# sm_watch.net
KiCad netlist of a schematic drawn in EAGLE
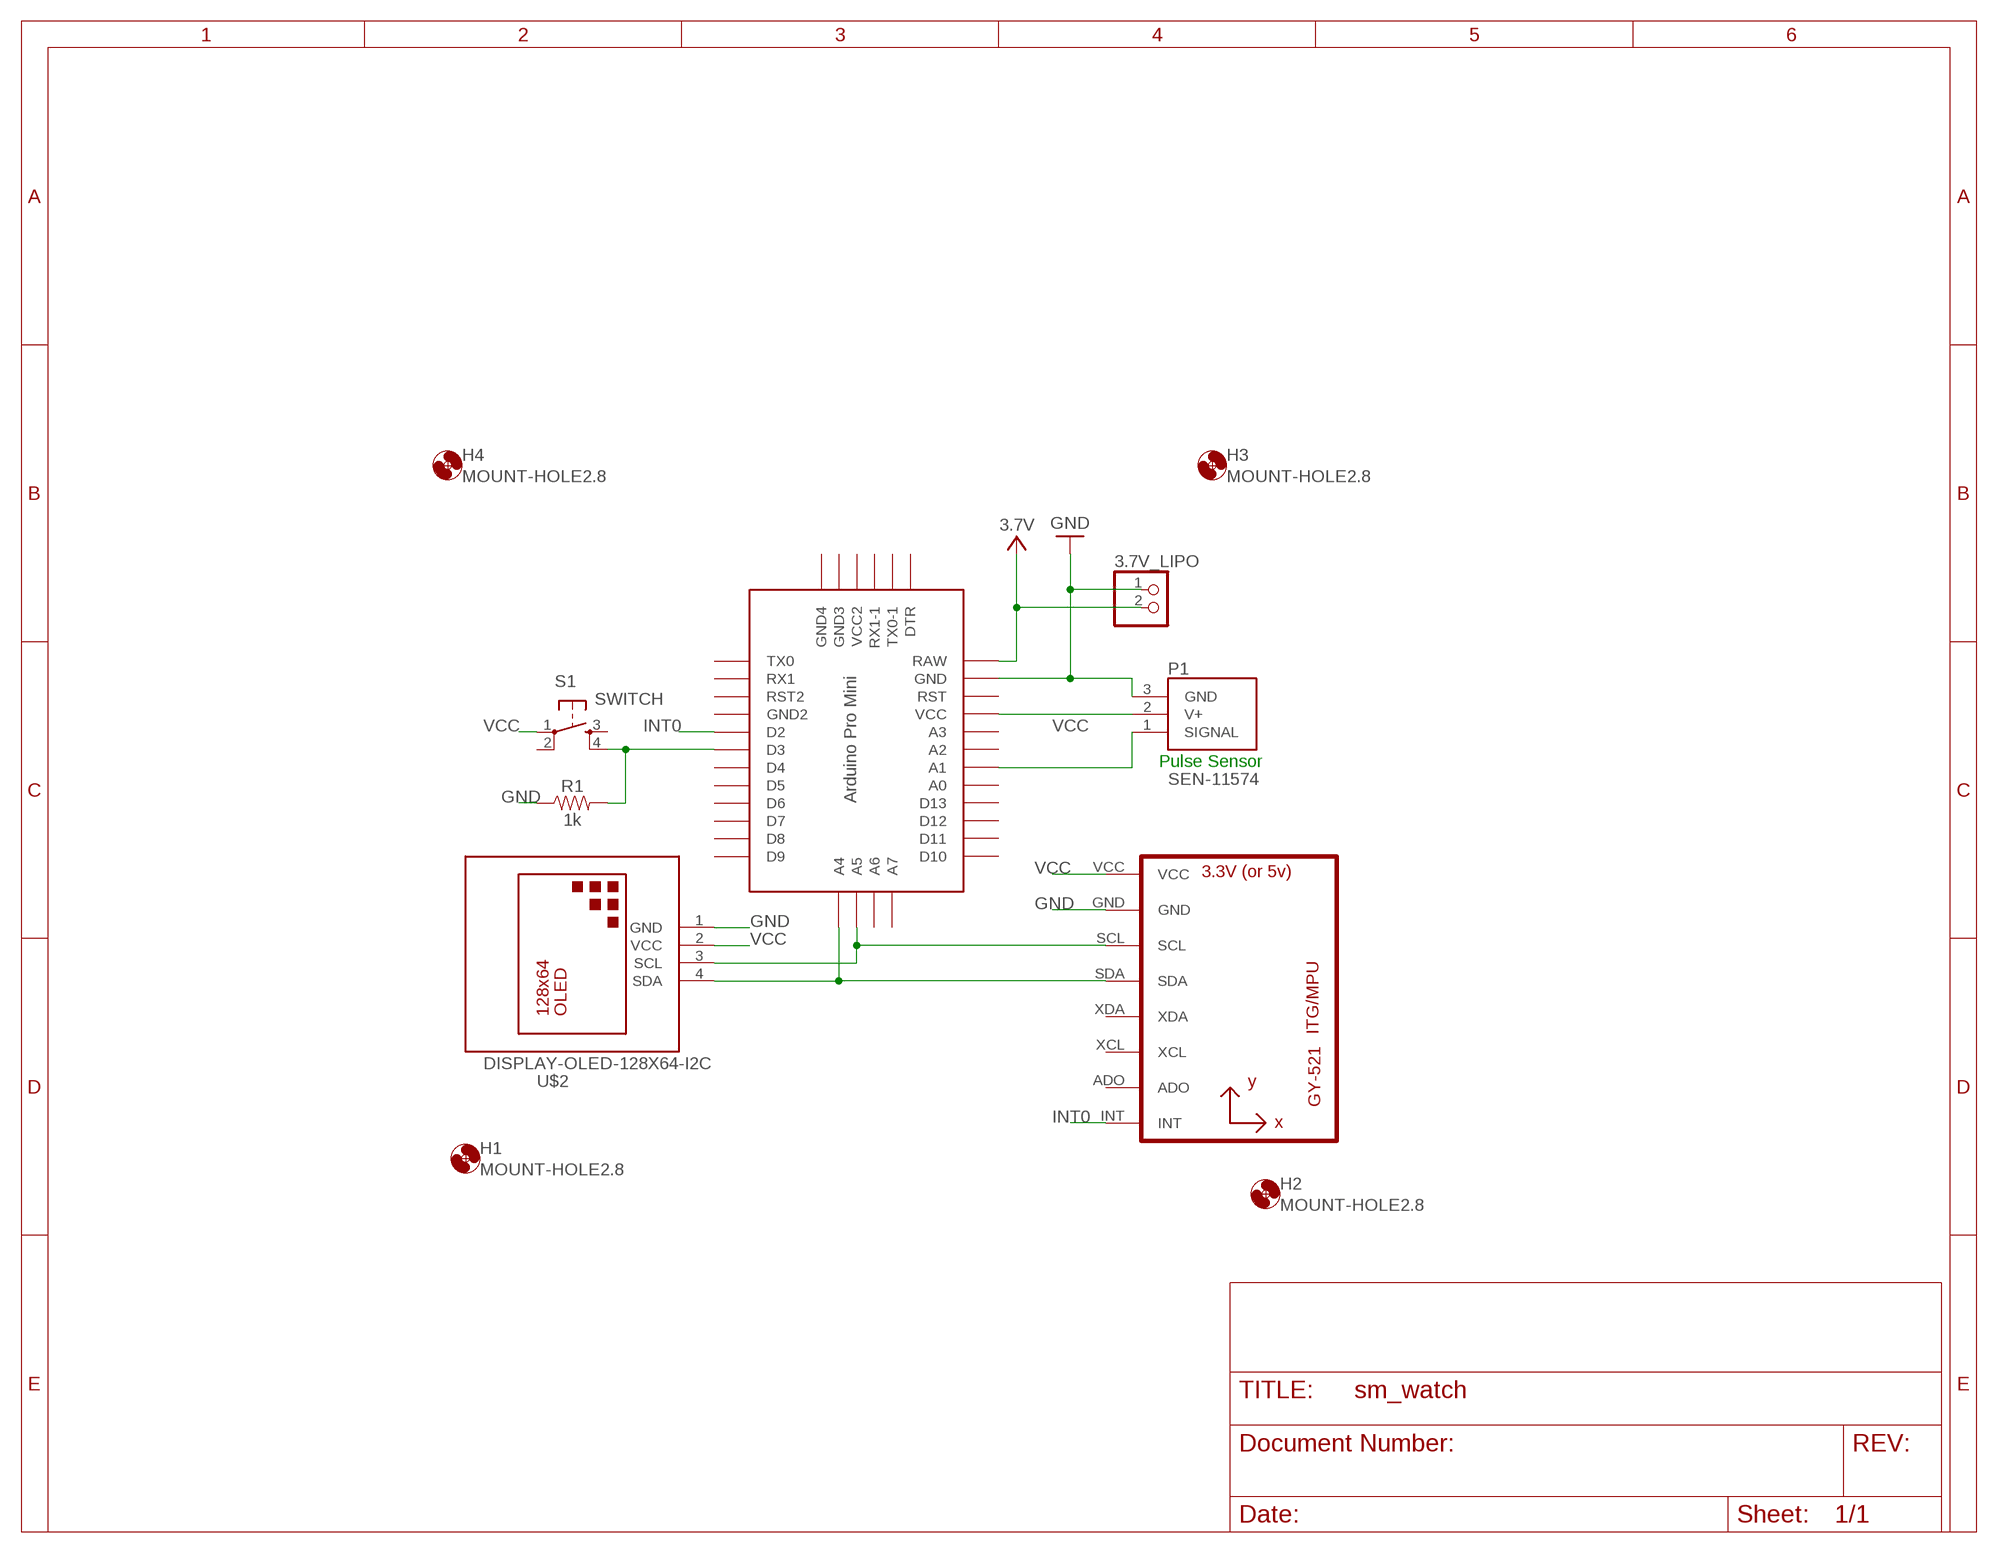
[diagram p0: schematic, sheet 1]

(export (version "E")
  (design (tool "Eeschema 10.0.6"))
  (components
    (comp (ref "3.7V_LIPO")
      (value "PINHD-1X2/90")
      (footprint "eagle-import:1X02_90")
      (libsource (lib "eagle-import") (part "PINHD-1X2/90"))
    )
    (comp (ref "H1")
      (value "MOUNT-HOLE2.8")
      (footprint "eagle-import:2,8")
      (libsource (lib "eagle-import") (part "MOUNT-HOLE2.8"))
    )
    (comp (ref "H2")
      (value "MOUNT-HOLE2.8")
      (footprint "eagle-import:2,8")
      (libsource (lib "eagle-import") (part "MOUNT-HOLE2.8"))
    )
    (comp (ref "H3")
      (value "MOUNT-HOLE2.8")
      (footprint "eagle-import:2,8")
      (libsource (lib "eagle-import") (part "MOUNT-HOLE2.8"))
    )
    (comp (ref "H4")
      (value "MOUNT-HOLE2.8")
      (footprint "eagle-import:2,8")
      (libsource (lib "eagle-import") (part "MOUNT-HOLE2.8"))
    )
    (comp (ref "P1")
      (value "SEN-11574")
      (footprint "eagle-import:XDCR_SEN-11574")
      (fields (field (name "MF") "SparkFun"))
      (libsource (lib "eagle-import") (part "SEN-11574"))
    )
    (comp (ref "R1")
      (value "1k")
      (footprint "eagle-import:0402-TIGHT")
      (libsource (lib "eagle-import") (part "1KOHM-0402T-1/16W-1%"))
    )
    (comp (ref "S1")
      (value "SWITCH")
      (footprint "eagle-import:DTS-6")
      (libsource (lib "eagle-import") (part "DTS-6"))
    )
    (comp (ref "U$1")
      (value "PRO-MINI")
      (footprint "eagle-import:PRO-MINI")
      (libsource (lib "eagle-import") (part "PRO-MINI"))
    )
    (comp (ref "U$2")
      (value "DISPLAY-OLED-128X64-I2C")
      (footprint "eagle-import:DISPLAY-OLED-128X64-I2C")
      (libsource (lib "eagle-import") (part "DISPLAY-OLED-128X64-I2C"))
    )
    (comp (ref "U1")
      (value "GY-521MPU6050")
      (footprint "eagle-import:GY-521")
      (libsource (lib "eagle-import") (part "GY-521MPU6050"))
    )
  )
  (nets
    (net (code "1") (name "/INT0") (class "Default")
      (node (ref "U$1") (pin "D2") (pinfunction "D2_D2") (pintype "bidirectional"))
      (node (ref "U1") (pin "INT") (pinfunction "INT_INT") (pintype "bidirectional"))
    )
    (net (code "2") (name "/VCC") (class "Default")
      (node (ref "P1") (pin "2") (pinfunction "V+_2") (pintype "power_in"))
      (node (ref "S1") (pin "1") (pinfunction "1_1") (pintype "passive"))
      (node (ref "U$1") (pin "VCC") (pinfunction "VCC_VCC") (pintype "bidirectional"))
      (node (ref "U$2") (pin "2") (pinfunction "VCC_2") (pintype "power_in"))
      (node (ref "U1") (pin "VCC") (pinfunction "VCC_VCC") (pintype "bidirectional"))
    )
    (net (code "3") (name "3.7V") (class "Default")
      (node (ref "3.7V_LIPO") (pin "2") (pinfunction "2_2") (pintype "passive"))
      (node (ref "U$1") (pin "RAW") (pinfunction "RAW_RAW") (pintype "power_in"))
    )
    (net (code "4") (name "GND") (class "Default")
      (node (ref "3.7V_LIPO") (pin "1") (pinfunction "1_1") (pintype "passive"))
      (node (ref "P1") (pin "3") (pinfunction "GND_3") (pintype "power_in"))
      (node (ref "R1") (pin "1") (pinfunction "1_1") (pintype "passive"))
      (node (ref "U$1") (pin "GND") (pinfunction "GND_GND") (pintype "input"))
      (node (ref "U$2") (pin "1") (pinfunction "GND_1") (pintype "power_in"))
      (node (ref "U1") (pin "GND") (pinfunction "GND_GND") (pintype "bidirectional"))
    )
    (net (code "5") (name "Net-(P1-SIGNAL)") (class "Default")
      (node (ref "P1") (pin "1") (pinfunction "SIGNAL_1") (pintype "bidirectional"))
      (node (ref "U$1") (pin "A1") (pinfunction "A1_A1") (pintype "bidirectional"))
    )
    (net (code "6") (name "Net-(R1-Pad2)") (class "Default")
      (node (ref "R1") (pin "2") (pinfunction "2_2") (pintype "passive"))
      (node (ref "S1") (pin "4") (pinfunction "4_4") (pintype "passive"))
      (node (ref "U$1") (pin "D3") (pinfunction "D3_D3") (pintype "bidirectional"))
    )
    (net (code "7") (name "Net-(U$2-SCL)") (class "Default")
      (node (ref "U$1") (pin "A5") (pinfunction "A5_A5") (pintype "bidirectional"))
      (node (ref "U$2") (pin "3") (pinfunction "SCL_3") (pintype "bidirectional"))
      (node (ref "U1") (pin "SCL") (pinfunction "SCL_SCL") (pintype "bidirectional"))
    )
    (net (code "8") (name "Net-(U$2-SDA)") (class "Default")
      (node (ref "U$1") (pin "A4") (pinfunction "A4_A4") (pintype "bidirectional"))
      (node (ref "U$2") (pin "4") (pinfunction "SDA_4") (pintype "bidirectional"))
      (node (ref "U1") (pin "SDA") (pinfunction "SDA_SDA") (pintype "bidirectional"))
    )
    (net (code "9") (name "unconnected-(S1-Pad2)") (class "Default")
      (node (ref "S1") (pin "2") (pinfunction "2_2") (pintype "passive"))
    )
    (net (code "10") (name "unconnected-(S1-Pad3)") (class "Default")
      (node (ref "S1") (pin "3") (pinfunction "3_3") (pintype "passive"))
    )
    (net (code "11") (name "unconnected-(U$1-GND2-PadGND1)") (class "Default")
      (node (ref "U$1") (pin "GND1") (pinfunction "GND2_GND1") (pintype "bidirectional"))
    )
    (net (code "12") (name "unconnected-(U$1-GND4-PadGND2)") (class "Default")
      (node (ref "U$1") (pin "GND2") (pinfunction "GND4_GND2") (pintype "bidirectional"))
    )
    (net (code "13") (name "unconnected-(U$1-PadA0)") (class "Default")
      (node (ref "U$1") (pin "A0") (pinfunction "A0_A0") (pintype "bidirectional"))
    )
    (net (code "14") (name "unconnected-(U$1-PadA2)") (class "Default")
      (node (ref "U$1") (pin "A2") (pinfunction "A2_A2") (pintype "bidirectional"))
    )
    (net (code "15") (name "unconnected-(U$1-PadA3)") (class "Default")
      (node (ref "U$1") (pin "A3") (pinfunction "A3_A3") (pintype "bidirectional"))
    )
    (net (code "16") (name "unconnected-(U$1-PadA6)") (class "Default")
      (node (ref "U$1") (pin "A6") (pinfunction "A6_A6") (pintype "bidirectional"))
    )
    (net (code "17") (name "unconnected-(U$1-PadA7)") (class "Default")
      (node (ref "U$1") (pin "A7") (pinfunction "A7_A7") (pintype "bidirectional"))
    )
    (net (code "18") (name "unconnected-(U$1-PadD4)") (class "Default")
      (node (ref "U$1") (pin "D4") (pinfunction "D4_D4") (pintype "bidirectional"))
    )
    (net (code "19") (name "unconnected-(U$1-PadD5)") (class "Default")
      (node (ref "U$1") (pin "D5") (pinfunction "D5_D5") (pintype "bidirectional"))
    )
    (net (code "20") (name "unconnected-(U$1-PadD6)") (class "Default")
      (node (ref "U$1") (pin "D6") (pinfunction "D6_D6") (pintype "bidirectional"))
    )
    (net (code "21") (name "unconnected-(U$1-PadD7)") (class "Default")
      (node (ref "U$1") (pin "D7") (pinfunction "D7_D7") (pintype "bidirectional"))
    )
    (net (code "22") (name "unconnected-(U$1-PadD8)") (class "Default")
      (node (ref "U$1") (pin "D8") (pinfunction "D8_D8") (pintype "bidirectional"))
    )
    (net (code "23") (name "unconnected-(U$1-PadD9)") (class "Default")
      (node (ref "U$1") (pin "D9") (pinfunction "D9_D9") (pintype "bidirectional"))
    )
    (net (code "24") (name "unconnected-(U$1-PadD10)") (class "Default")
      (node (ref "U$1") (pin "D10") (pinfunction "D10_D10") (pintype "bidirectional"))
    )
    (net (code "25") (name "unconnected-(U$1-PadD11)") (class "Default")
      (node (ref "U$1") (pin "D11") (pinfunction "D11_D11") (pintype "bidirectional"))
    )
    (net (code "26") (name "unconnected-(U$1-PadD12)") (class "Default")
      (node (ref "U$1") (pin "D12") (pinfunction "D12_D12") (pintype "bidirectional"))
    )
    (net (code "27") (name "unconnected-(U$1-PadD13)") (class "Default")
      (node (ref "U$1") (pin "D13") (pinfunction "D13_D13") (pintype "bidirectional"))
    )
    (net (code "28") (name "unconnected-(U$1-PadDTR)") (class "Default")
      (node (ref "U$1") (pin "DTR") (pinfunction "DTR_DTR") (pintype "bidirectional"))
    )
    (net (code "29") (name "unconnected-(U$1-PadGND3)") (class "Default")
      (node (ref "U$1") (pin "GND3") (pinfunction "GND3_GND3") (pintype "bidirectional"))
    )
    (net (code "30") (name "unconnected-(U$1-PadRST)") (class "Default")
      (node (ref "U$1") (pin "RST") (pinfunction "RST_RST") (pintype "bidirectional"))
    )
    (net (code "31") (name "unconnected-(U$1-PadRX1)") (class "Default")
      (node (ref "U$1") (pin "RX1") (pinfunction "RX1_RX1") (pintype "bidirectional"))
    )
    (net (code "32") (name "unconnected-(U$1-PadRX1-1)") (class "Default")
      (node (ref "U$1") (pin "RX1-1") (pinfunction "RX1-1_RX1-1") (pintype "bidirectional"))
    )
    (net (code "33") (name "unconnected-(U$1-PadTX0)") (class "Default")
      (node (ref "U$1") (pin "TX0") (pinfunction "TX0_TX0") (pintype "bidirectional"))
    )
    (net (code "34") (name "unconnected-(U$1-PadTX0-1)") (class "Default")
      (node (ref "U$1") (pin "TX0-1") (pinfunction "TX0-1_TX0-1") (pintype "bidirectional"))
    )
    (net (code "35") (name "unconnected-(U$1-RST2-PadRST1)") (class "Default")
      (node (ref "U$1") (pin "RST1") (pinfunction "RST2_RST1") (pintype "bidirectional"))
    )
    (net (code "36") (name "unconnected-(U$1-VCC2-PadVCC1)") (class "Default")
      (node (ref "U$1") (pin "VCC1") (pinfunction "VCC2_VCC1") (pintype "bidirectional"))
    )
    (net (code "37") (name "unconnected-(U1-PadADO)") (class "Default")
      (node (ref "U1") (pin "ADO") (pinfunction "ADO_ADO") (pintype "bidirectional"))
    )
    (net (code "38") (name "unconnected-(U1-PadXCL)") (class "Default")
      (node (ref "U1") (pin "XCL") (pinfunction "XCL_XCL") (pintype "bidirectional"))
    )
    (net (code "39") (name "unconnected-(U1-PadXDA)") (class "Default")
      (node (ref "U1") (pin "XDA") (pinfunction "XDA_XDA") (pintype "bidirectional"))
    )
  )
)
